# UVS-SCH-1.net
KiCad netlist of a schematic drawn in Altium Designer
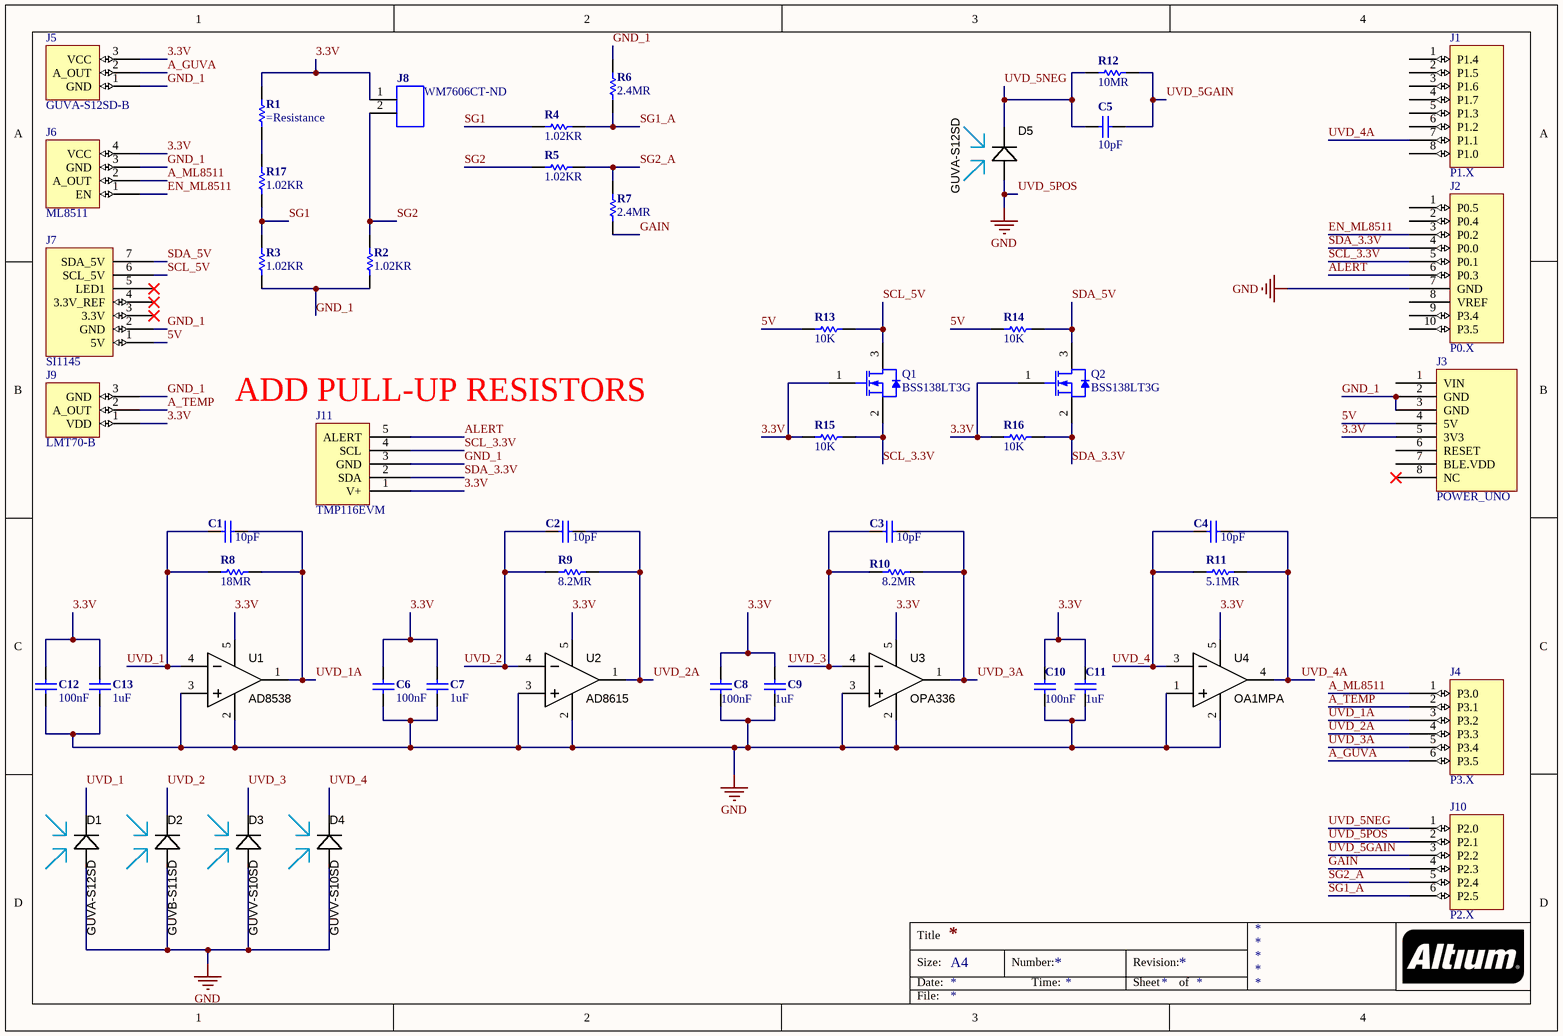
[diagram p0: UVS-SCH-1.SchDoc]

(export (version "E")
  (design (tool "Eeschema 10.0.6"))
  (components
    (comp (ref "C1")
      (value "10pF")
      (footprint "CAP-0805(2012)-R")
      (description "___ OHM ___ mW 0805(2012) SMD")
      (fields
        (field (name "MANUFACTURER") "Kemet")
        (field (name "MANUFACTURER PART NUMBER") "C0805C100J5GAC-TU")
      )
      (libsource (lib "UVS-Schlib") (part "C-0805(2012)"))
    )
    (comp (ref "C2")
      (value "10pF")
      (footprint "CAP-0805(2012)-R")
      (description "___ OHM ___ mW 0805(2012) SMD")
      (fields
        (field (name "MANUFACTURER") "Kemet")
        (field (name "MANUFACTURER PART NUMBER") "C0805C100J5GAC-TU")
      )
      (libsource (lib "UVS-Schlib") (part "C-0805(2012)"))
    )
    (comp (ref "C3")
      (value "10pF")
      (footprint "CAP-0805(2012)-R")
      (description "___ OHM ___ mW 0805(2012) SMD")
      (fields
        (field (name "MANUFACTURER") "Kemet")
        (field (name "MANUFACTURER PART NUMBER") "C0805C100J5GAC-TU")
      )
      (libsource (lib "UVS-Schlib") (part "C-0805(2012)"))
    )
    (comp (ref "C4")
      (value "10pF")
      (footprint "CAP-0805(2012)-R")
      (description "___ OHM ___ mW 0805(2012) SMD")
      (fields
        (field (name "MANUFACTURER") "Kemet")
        (field (name "MANUFACTURER PART NUMBER") "C0805C100J5GAC-TU")
      )
      (libsource (lib "UVS-Schlib") (part "C-0805(2012)"))
    )
    (comp (ref "C5")
      (value "10pF")
      (footprint "CAP-0805(2012)-R")
      (description "___ OHM ___ mW 0805(2012) SMD")
      (fields
        (field (name "MANUFACTURER") "KEMET")
        (field (name "MANUFACTURER PART NUMBER") "C0805C100J5GAC-TU")
      )
      (libsource (lib "UVS-Schlib") (part "C-0805(2012)"))
    )
    (comp (ref "C6")
      (value "100nF")
      (footprint "CAP-0805(2012)-R")
      (description "___ OHM ___ mW 0805(2012) SMD")
      (fields
        (field (name "MANUFACTURER") "Yageo")
        (field (name "MANUFACTURER PART NUMBER") "CC0805KRX7R9BB104")
      )
      (libsource (lib "UVS-Schlib") (part "C-0805(2012)"))
    )
    (comp (ref "C7")
      (value "1uF")
      (footprint "CAP-0805(2012)-R")
      (description "___ OHM ___ mW 0805(2012) SMD")
      (fields
        (field (name "MANUFACTURER") "Yageo")
        (field (name "MANUFACTURER PART NUMBER") "CC0805KKX7R7BB105")
      )
      (libsource (lib "UVS-Schlib") (part "C-0805(2012)"))
    )
    (comp (ref "C8")
      (value "100nF")
      (footprint "CAP-0805(2012)-R")
      (description "___ OHM ___ mW 0805(2012) SMD")
      (fields
        (field (name "MANUFACTURER") "Yageo")
        (field (name "MANUFACTURER PART NUMBER") "CC0805KRX7R9BB104")
      )
      (libsource (lib "UVS-Schlib") (part "C-0805(2012)"))
    )
    (comp (ref "C9")
      (value "1uF")
      (footprint "CAP-0805(2012)-R")
      (description "___ OHM ___ mW 0805(2012) SMD")
      (fields
        (field (name "MANUFACTURER") "Yageo")
        (field (name "MANUFACTURER PART NUMBER") "CC0805KKX7R7BB105")
      )
      (libsource (lib "UVS-Schlib") (part "C-0805(2012)"))
    )
    (comp (ref "C10")
      (value "100nF")
      (footprint "CAP-0805(2012)-R")
      (description "___ OHM ___ mW 0805(2012) SMD")
      (fields
        (field (name "MANUFACTURER") "Yageo")
        (field (name "MANUFACTURER PART NUMBER") "CC0805KRX7R9BB104")
      )
      (libsource (lib "UVS-Schlib") (part "C-0805(2012)"))
    )
    (comp (ref "C11")
      (value "1uF")
      (footprint "CAP-0805(2012)-R")
      (description "___ OHM ___ mW 0805(2012) SMD")
      (fields
        (field (name "MANUFACTURER") "Yageo")
        (field (name "MANUFACTURER PART NUMBER") "CC0805KKX7R7BB105")
      )
      (libsource (lib "UVS-Schlib") (part "C-0805(2012)"))
    )
    (comp (ref "C12")
      (value "100nF")
      (footprint "CAP-0805(2012)-R")
      (description "___ OHM ___ mW 0805(2012) SMD")
      (fields
        (field (name "MANUFACTURER") "Yageo")
        (field (name "MANUFACTURER PART NUMBER") "CC0805KRX7R9BB104")
      )
      (libsource (lib "UVS-Schlib") (part "C-0805(2012)"))
    )
    (comp (ref "C13")
      (value "1uF")
      (footprint "CAP-0805(2012)-R")
      (description "___ OHM ___ mW 0805(2012) SMD")
      (fields
        (field (name "MANUFACTURER") "Yageo")
        (field (name "MANUFACTURER PART NUMBER") "CC0805KKX7R7BB105")
      )
      (libsource (lib "UVS-Schlib") (part "C-0805(2012)"))
    )
    (comp (ref "D1")
      (value "GUVA-S12SD")
      (footprint "SMD 3528")
      (description "UV Photodiode, 3528 SMD")
      (libsource (lib "UVS-Schlib") (part "GUVA-S12SD"))
    )
    (comp (ref "D2")
      (value "GUVB-S11SD")
      (footprint "SMD 3528")
      (description "UV Photodiode, 3528 SMD")
      (libsource (lib "UVS-Schlib") (part "GUVB-S11SD"))
    )
    (comp (ref "D3")
      (value "GUVV-S10SD")
      (footprint "SMD 3528")
      (description "UV Photodiode, 3528 SMD")
      (libsource (lib "UVS-Schlib") (part "GUVV-S10SD"))
    )
    (comp (ref "D4")
      (value "GUVV-S10SD")
      (footprint "SMD 3528")
      (description "UV Photodiode, 3528 SMD")
      (libsource (lib "UVS-Schlib") (part "GUVV-S10SD"))
    )
    (comp (ref "D5")
      (value "GUVA-S12SD")
      (footprint "SMD 3528")
      (description "UV Photodiode, 3528 SMD")
      (libsource (lib "UVS-Schlib") (part "GUVA-S12SD"))
    )
    (comp (ref "J1")
      (value "P1.X")
      (footprint "Header 8x1 8.5mm")
      (libsource (lib "UVS-Schlib") (part "IOL"))
    )
    (comp (ref "J2")
      (value "P0.X")
      (footprint "Header 10x1 8.5mm")
      (libsource (lib "UVS-Schlib") (part "IOH"))
    )
    (comp (ref "J3")
      (value "POWER_UNO")
      (footprint "Header 8x1 8.5mm")
      (libsource (lib "UVS-Schlib") (part "POWER_UNO"))
    )
    (comp (ref "J4") (value "P3.X") (footprint "Header 6x1 8.5mm") (libsource (lib "UVS-Schlib") (part "AD")))
    (comp (ref "J5")
      (value "GUVA-S12SD-B")
      (footprint "UVS-PcbLib:Header 3x1 8.5mm")
      (description "UV Light Sensor Breakout Board")
      (libsource (lib "UVS-Schlib") (part "GUVA-S12SD-B"))
    )
    (comp (ref "J6")
      (value "ML8511")
      (footprint "UVS-PcbLib:Header 4x1 8.5mm")
      (description "UV Light Sensor Breakout Board")
      (libsource (lib "UVS-Schlib") (part "ML8511"))
    )
    (comp (ref "J7")
      (value "SI1145")
      (footprint "UVS-PcbLib:Header 7x1 8.5mm")
      (description "UV Light Sensor Digital")
      (libsource (lib "UVS-Schlib") (part "SI1145"))
    )
    (comp (ref "J8")
      (value "Header 2 pin")
      (footprint "WM7606CT-ND")
      (description "Header, 2 pin, .1 pitch")
      (fields
        (field (name "MANUFACTURER") "Molex, LLC")
        (field (name "MANUFACTURER PART NUMBER") "0533980271")
        (field (name "SUPPLIER PART NUMBER 1") "WM7606CT-ND")
      )
      (libsource (lib "UVS-Schlib") (part "CON-2Pin"))
    )
    (comp (ref "J9")
      (value "LMT70-B")
      (footprint "UVS-PcbLib:Header 3x1 8.5mm")
      (description "Precision Analog Temperature Sensor")
      (libsource (lib "UVS-Schlib") (part "LMT70-B"))
    )
    (comp (ref "J10")
      (value "P2.X")
      (footprint "Header 6x1 8.5mm")
      (libsource (lib "UVS-Schlib") (part "P2.X"))
    )
    (comp (ref "J11")
      (value "TMP116EVM")
      (footprint "Header 5x1 8.5mm")
      (libsource (lib "UVS-Schlib") (part "TMP116EVM"))
    )
    (comp (ref "Q1")
      (value "BSS138LT3G")
      (footprint "ONSC-SOT-23-3-318-08_V")
      (description "Power MOSFET, 200 mA, 50 V, N-Channel, 3-Pin SOT-23, Pb-Free, Tape and Reel")
      (fields (field (name "MANUFACTURER") "ON Semiconductor"))
      (libsource (lib "Altium Content Vault") (part "CMP-1058-00765-1"))
    )
    (comp (ref "Q2")
      (value "BSS138LT3G")
      (footprint "ONSC-SOT-23-3-318-08_V")
      (description "Power MOSFET, 200 mA, 50 V, N-Channel, 3-Pin SOT-23, Pb-Free, Tape and Reel")
      (fields (field (name "MANUFACTURER") "ON Semiconductor"))
      (libsource (lib "Altium Content Vault") (part "CMP-1058-00765-1"))
    )
    (comp (ref "R1")
      (value "~")
      (footprint "R-0805(2012)-R")
      (description "___ OHM ___ mW 0805(2012) SMD")
      (libsource (lib "UVS-Schlib") (part "R-0805(2012)"))
    )
    (comp (ref "R2")
      (value "1.02KR")
      (footprint "R-0805(2012)-R")
      (description "___ OHM ___ mW 0805(2012) SMD")
      (fields
        (field (name "MANUFACTURER") "Panasonic")
        (field (name "MANUFACTURER PART NUMBER") "ERA6AEB1021V")
      )
      (libsource (lib "UVS-Schlib") (part "R-0805(2012)"))
    )
    (comp (ref "R3")
      (value "1.02KR")
      (footprint "R-0805(2012)-R")
      (description "___ OHM ___ mW 0805(2012) SMD")
      (fields
        (field (name "MANUFACTURER") "Panasonic")
        (field (name "MANUFACTURER PART NUMBER") "ERA6AEB1021V")
      )
      (libsource (lib "UVS-Schlib") (part "R-0805(2012)"))
    )
    (comp (ref "R4")
      (value "1.02KR")
      (footprint "R-0805(2012)-R")
      (description "___ OHM ___ mW 0805(2012) SMD")
      (fields
        (field (name "MANUFACTURER") "Panasonic")
        (field (name "MANUFACTURER PART NUMBER") "ERA6AEB1021V")
      )
      (libsource (lib "UVS-Schlib") (part "R-0805(2012)"))
    )
    (comp (ref "R5")
      (value "1.02KR")
      (footprint "R-0805(2012)-R")
      (description "___ OHM ___ mW 0805(2012) SMD")
      (fields
        (field (name "MANUFACTURER") "Panasonic")
        (field (name "MANUFACTURER PART NUMBER") "ERA6AEB1021V")
      )
      (libsource (lib "UVS-Schlib") (part "R-0805(2012)"))
    )
    (comp (ref "R6")
      (value "2.4MR")
      (footprint "R-0805(2012)-R")
      (description "___ OHM ___ mW 0805(2012) SMD")
      (fields
        (field (name "MANUFACTURER") "Panasonic ECG")
        (field (name "MANUFACTURER PART NUMBER") "ERJ-6GEYJ245V")
      )
      (libsource (lib "UVS-Schlib") (part "R-0805(2012)"))
    )
    (comp (ref "R7")
      (value "2.4MR")
      (footprint "R-0805(2012)-R")
      (description "___ OHM ___ mW 0805(2012) SMD")
      (fields
        (field (name "MANUFACTURER") "Panasonic ECG")
        (field (name "MANUFACTURER PART NUMBER") "ERJ-6GEYJ245V")
      )
      (libsource (lib "UVS-Schlib") (part "R-0805(2012)"))
    )
    (comp (ref "R8")
      (value "18MR")
      (footprint "R-0805(2012)-R")
      (description "___ OHM ___ mW 0805(2012) SMD")
      (fields
        (field (name "MANUFACTURER") "Yageo")
        (field (name "MANUFACTURER PART NUMBER") "RC0805JR-0718ML")
      )
      (libsource (lib "UVS-Schlib") (part "R-0805(2012)"))
    )
    (comp (ref "R9")
      (value "8.2MR")
      (footprint "R-0805(2012)-R")
      (description "___ OHM ___ mW 0805(2012) SMD")
      (fields
        (field (name "MANUFACTURER") "Yageo")
        (field (name "MANUFACTURER PART NUMBER") "RC0805FR-078M2L")
      )
      (libsource (lib "UVS-Schlib") (part "R-0805(2012)"))
    )
    (comp (ref "R10")
      (value "8.2MR")
      (footprint "R-0805(2012)-R")
      (description "___ OHM ___ mW 0805(2012) SMD")
      (fields
        (field (name "MANUFACTURER") "Yageo")
        (field (name "MANUFACTURER PART NUMBER") "RC0805FR-078M2L")
      )
      (libsource (lib "UVS-Schlib") (part "R-0805(2012)"))
    )
    (comp (ref "R11")
      (value "5.1MR")
      (footprint "R-0805(2012)-R")
      (description "___ OHM ___ mW 0805(2012) SMD")
      (fields
        (field (name "MANUFACTURER") "Yageo")
        (field (name "MANUFACTURER PART NUMBER") "RC0805FR-075M1L")
      )
      (libsource (lib "UVS-Schlib") (part "R-0805(2012)"))
    )
    (comp (ref "R12")
      (value "10MR")
      (footprint "R-0805(2012)-R")
      (description "___ OHM ___ mW 0805(2012) SMD")
      (fields
        (field (name "MANUFACTURER") "Yageo")
        (field (name "MANUFACTURER PART NUMBER") "RC0805JR-0710ML")
      )
      (libsource (lib "UVS-Schlib") (part "R-0805(2012)"))
    )
    (comp (ref "R13")
      (value "10K")
      (footprint "R-0805(2012)-R")
      (description "___ OHM ___ mW 0805(2012) SMD")
      (fields
        (field (name "MANUFACTURER") "Yageo")
        (field (name "MANUFACTURER PART NUMBER") "RC0805FR-0710KL")
      )
      (libsource (lib "UVS-Schlib") (part "R-0805(2012)"))
    )
    (comp (ref "R14")
      (value "10K")
      (footprint "R-0805(2012)-R")
      (description "___ OHM ___ mW 0805(2012) SMD")
      (fields
        (field (name "MANUFACTURER") "Yageo")
        (field (name "MANUFACTURER PART NUMBER") "RC0805FR-0710KL")
      )
      (libsource (lib "UVS-Schlib") (part "R-0805(2012)"))
    )
    (comp (ref "R15")
      (value "10K")
      (footprint "R-0805(2012)-R")
      (description "___ OHM ___ mW 0805(2012) SMD")
      (fields
        (field (name "MANUFACTURER") "Yageo")
        (field (name "MANUFACTURER PART NUMBER") "RC0805FR-0710KL")
      )
      (libsource (lib "UVS-Schlib") (part "R-0805(2012)"))
    )
    (comp (ref "R16")
      (value "10K")
      (footprint "R-0805(2012)-R")
      (description "___ OHM ___ mW 0805(2012) SMD")
      (fields
        (field (name "MANUFACTURER") "Yageo")
        (field (name "MANUFACTURER PART NUMBER") "RC0805FR-0710KL")
      )
      (libsource (lib "UVS-Schlib") (part "R-0805(2012)"))
    )
    (comp (ref "R17")
      (value "1.02KR")
      (footprint "R-0805(2012)-R")
      (description "___ OHM ___ mW 0805(2012) SMD")
      (fields
        (field (name "MANUFACTURER") "Panasonic")
        (field (name "MANUFACTURER PART NUMBER") "ERA6AEB1021V")
      )
      (libsource (lib "UVS-Schlib") (part "R-0805(2012)"))
    )
    (comp (ref "U1")
      (value "AD8538")
      (footprint "SOT23-5")
      (description "IC SMD Atuo-Zero Op Amp Precision, Low Power")
      (fields
        (field (name "MANUFACTURER") "Analog Devices")
        (field (name "MANUFACTURER PART NUMBER") "AD8538AUJZ-REEL7")
      )
      (libsource (lib "UVS-Schlib") (part "AD8538"))
    )
    (comp (ref "U2")
      (value "AD8615")
      (footprint "SOT23-5")
      (description "IC SMD Transimpedance Op Amp Precision")
      (fields
        (field (name "MANUFACTURER") "Analog Devices")
        (field (name "MANUFACTURER PART NUMBER") "AD8615AUJZ-REEL7")
      )
      (libsource (lib "UVS-Schlib") (part "AD8615"))
    )
    (comp (ref "U3")
      (value "OPA336")
      (footprint "SOT23-5")
      (fields
        (field (name "MANUFACTURER") "Texas Instruments")
        (field (name "MANUFACTURER PART NUMBER") "OPA336NA/3K")
      )
      (libsource (lib "UVS-Schlib") (part "OPA336"))
    )
    (comp (ref "U4")
      (value "OA1MPA")
      (footprint "SC70-5L")
      (fields
        (field (name "MANUFACTURER") "STMicroelectronics")
        (field (name "MANUFACTURER PART NUMBER") "OA1MPA22C")
      )
      (libsource (lib "UVS-Schlib") (part "OA1MPA"))
    )
  )
  (nets
    (net (code "1") (name "/3.3V") (class "Default")
      (node (ref "C10") (pin "1") (pinfunction "1_1") (pintype "passive"))
      (node (ref "C11") (pin "1") (pinfunction "1_1") (pintype "passive"))
      (node (ref "C12") (pin "1") (pinfunction "1_1") (pintype "passive"))
      (node (ref "C13") (pin "1") (pinfunction "1_1") (pintype "passive"))
      (node (ref "C6") (pin "1") (pinfunction "1_1") (pintype "passive"))
      (node (ref "C7") (pin "1") (pinfunction "1_1") (pintype "passive"))
      (node (ref "C8") (pin "1") (pinfunction "1_1") (pintype "passive"))
      (node (ref "C9") (pin "1") (pinfunction "1_1") (pintype "passive"))
      (node (ref "J11") (pin "1") (pinfunction "V+_1") (pintype "passive"))
      (node (ref "J3") (pin "5") (pinfunction "3V3_5") (pintype "power_in"))
      (node (ref "J5") (pin "3") (pinfunction "VCC_3") (pintype "bidirectional"))
      (node (ref "J6") (pin "4") (pinfunction "VCC_4") (pintype "bidirectional"))
      (node (ref "J8") (pin "1") (pinfunction "1_1") (pintype "passive"))
      (node (ref "J9") (pin "1") (pinfunction "VDD_1") (pintype "bidirectional"))
      (node (ref "Q1") (pin "1") (pinfunction "G_1") (pintype "passive"))
      (node (ref "Q2") (pin "1") (pinfunction "G_1") (pintype "passive"))
      (node (ref "R1") (pin "1") (pinfunction "1_1") (pintype "passive"))
      (node (ref "R15") (pin "1") (pinfunction "1_1") (pintype "passive"))
      (node (ref "R16") (pin "1") (pinfunction "1_1") (pintype "passive"))
      (node (ref "U1") (pin "5") (pinfunction "V+_5") (pintype "passive"))
      (node (ref "U2") (pin "5") (pinfunction "V+_5") (pintype "passive"))
      (node (ref "U3") (pin "5") (pinfunction "V+_5") (pintype "passive"))
      (node (ref "U4") (pin "5") (pinfunction "V+_5") (pintype "passive"))
    )
    (net (code "2") (name "/5V") (class "Default")
      (node (ref "J3") (pin "4") (pinfunction "5V_4") (pintype "power_in"))
      (node (ref "J7") (pin "1") (pinfunction "5V_1") (pintype "bidirectional"))
      (node (ref "R13") (pin "1") (pinfunction "1_1") (pintype "passive"))
      (node (ref "R14") (pin "1") (pinfunction "1_1") (pintype "passive"))
    )
    (net (code "3") (name "/ALERT") (class "Default")
      (node (ref "J11") (pin "5") (pinfunction "ALERT_5") (pintype "passive"))
      (node (ref "J2") (pin "6") (pinfunction "P0.3_6") (pintype "bidirectional"))
    )
    (net (code "4") (name "/A_GUVA") (class "Default")
      (node (ref "J4") (pin "6") (pinfunction "P3.5_6") (pintype "bidirectional"))
      (node (ref "J5") (pin "2") (pinfunction "A_OUT_2") (pintype "bidirectional"))
    )
    (net (code "5") (name "/A_ML8511") (class "Default")
      (node (ref "J4") (pin "1") (pinfunction "P3.0_1") (pintype "bidirectional"))
      (node (ref "J6") (pin "2") (pinfunction "A_OUT_2") (pintype "bidirectional"))
    )
    (net (code "6") (name "/A_TEMP") (class "Default")
      (node (ref "J4") (pin "2") (pinfunction "P3.1_2") (pintype "bidirectional"))
      (node (ref "J9") (pin "2") (pinfunction "A_OUT_2") (pintype "bidirectional"))
    )
    (net (code "7") (name "/EN_ML8511") (class "Default")
      (node (ref "J2") (pin "3") (pinfunction "P0.2_3") (pintype "bidirectional"))
      (node (ref "J6") (pin "1") (pinfunction "EN_1") (pintype "bidirectional"))
    )
    (net (code "8") (name "/GAIN") (class "Default")
      (node (ref "J10") (pin "4") (pinfunction "P2.3_4") (pintype "bidirectional"))
      (node (ref "R7") (pin "2") (pinfunction "2_2") (pintype "passive"))
    )
    (net (code "9") (name "/GND_1") (class "Default")
      (node (ref "J11") (pin "3") (pinfunction "GND_3") (pintype "passive"))
      (node (ref "J3") (pin "2") (pinfunction "GND_2") (pintype "power_in"))
      (node (ref "J3") (pin "3") (pinfunction "GND_3") (pintype "power_in"))
      (node (ref "J5") (pin "1") (pinfunction "GND_1") (pintype "bidirectional"))
      (node (ref "J6") (pin "3") (pinfunction "GND_3") (pintype "bidirectional"))
      (node (ref "J7") (pin "2") (pinfunction "GND_2") (pintype "bidirectional"))
      (node (ref "J9") (pin "3") (pinfunction "GND_3") (pintype "bidirectional"))
      (node (ref "R2") (pin "2") (pinfunction "2_2") (pintype "passive"))
      (node (ref "R3") (pin "2") (pinfunction "2_2") (pintype "passive"))
      (node (ref "R6") (pin "1") (pinfunction "1_1") (pintype "passive"))
    )
    (net (code "10") (name "/SCL_3.3V") (class "Default")
      (node (ref "J11") (pin "4") (pinfunction "SCL_4") (pintype "passive"))
      (node (ref "J2") (pin "5") (pinfunction "P0.1_5") (pintype "bidirectional"))
      (node (ref "Q1") (pin "2") (pinfunction "S_2") (pintype "passive"))
      (node (ref "R15") (pin "2") (pinfunction "2_2") (pintype "passive"))
    )
    (net (code "11") (name "/SCL_5V") (class "Default")
      (node (ref "J7") (pin "6") (pinfunction "SCL_5V_6") (pintype "passive"))
      (node (ref "Q1") (pin "3") (pinfunction "D_3") (pintype "passive"))
      (node (ref "R13") (pin "2") (pinfunction "2_2") (pintype "passive"))
    )
    (net (code "12") (name "/SDA_3.3V") (class "Default")
      (node (ref "J11") (pin "2") (pinfunction "SDA_2") (pintype "passive"))
      (node (ref "J2") (pin "4") (pinfunction "P0.0_4") (pintype "bidirectional"))
      (node (ref "Q2") (pin "2") (pinfunction "S_2") (pintype "passive"))
      (node (ref "R16") (pin "2") (pinfunction "2_2") (pintype "passive"))
    )
    (net (code "13") (name "/SDA_5V") (class "Default")
      (node (ref "J7") (pin "7") (pinfunction "SDA_5V_7") (pintype "passive"))
      (node (ref "Q2") (pin "3") (pinfunction "D_3") (pintype "passive"))
      (node (ref "R14") (pin "2") (pinfunction "2_2") (pintype "passive"))
    )
    (net (code "14") (name "/SG1") (class "Default")
      (node (ref "R17") (pin "2") (pinfunction "2_2") (pintype "passive"))
      (node (ref "R3") (pin "1") (pinfunction "1_1") (pintype "passive"))
      (node (ref "R4") (pin "1") (pinfunction "1_1") (pintype "passive"))
    )
    (net (code "15") (name "/SG1_A") (class "Default")
      (node (ref "J10") (pin "6") (pinfunction "P2.5_6") (pintype "bidirectional"))
      (node (ref "R4") (pin "2") (pinfunction "2_2") (pintype "passive"))
      (node (ref "R6") (pin "2") (pinfunction "2_2") (pintype "passive"))
    )
    (net (code "16") (name "/SG2") (class "Default")
      (node (ref "J8") (pin "2") (pinfunction "2_2") (pintype "passive"))
      (node (ref "R2") (pin "1") (pinfunction "1_1") (pintype "passive"))
      (node (ref "R5") (pin "1") (pinfunction "1_1") (pintype "passive"))
    )
    (net (code "17") (name "/SG2_A") (class "Default")
      (node (ref "J10") (pin "5") (pinfunction "P2.4_5") (pintype "bidirectional"))
      (node (ref "R5") (pin "2") (pinfunction "2_2") (pintype "passive"))
      (node (ref "R7") (pin "1") (pinfunction "1_1") (pintype "passive"))
    )
    (net (code "18") (name "/UVD_1") (class "Default")
      (node (ref "C1") (pin "1") (pinfunction "1_1") (pintype "passive"))
      (node (ref "D1") (pin "K") (pinfunction "K_K") (pintype "passive"))
      (node (ref "R8") (pin "1") (pinfunction "1_1") (pintype "passive"))
      (node (ref "U1") (pin "4") (pinfunction "IN-_4") (pintype "passive"))
    )
    (net (code "19") (name "/UVD_1A") (class "Default")
      (node (ref "C1") (pin "2") (pinfunction "2_2") (pintype "passive"))
      (node (ref "J4") (pin "3") (pinfunction "P3.2_3") (pintype "bidirectional"))
      (node (ref "R8") (pin "2") (pinfunction "2_2") (pintype "passive"))
      (node (ref "U1") (pin "1") (pinfunction "OUT_1") (pintype "passive"))
    )
    (net (code "20") (name "/UVD_2") (class "Default")
      (node (ref "C2") (pin "1") (pinfunction "1_1") (pintype "passive"))
      (node (ref "D2") (pin "K") (pinfunction "K_K") (pintype "passive"))
      (node (ref "R9") (pin "1") (pinfunction "1_1") (pintype "passive"))
      (node (ref "U2") (pin "4") (pinfunction "IN-_4") (pintype "passive"))
    )
    (net (code "21") (name "/UVD_2A") (class "Default")
      (node (ref "C2") (pin "2") (pinfunction "2_2") (pintype "passive"))
      (node (ref "J4") (pin "4") (pinfunction "P3.3_4") (pintype "bidirectional"))
      (node (ref "R9") (pin "2") (pinfunction "2_2") (pintype "passive"))
      (node (ref "U2") (pin "1") (pinfunction "OUT_1") (pintype "passive"))
    )
    (net (code "22") (name "/UVD_3") (class "Default")
      (node (ref "C3") (pin "1") (pinfunction "1_1") (pintype "passive"))
      (node (ref "D3") (pin "K") (pinfunction "K_K") (pintype "passive"))
      (node (ref "R10") (pin "1") (pinfunction "1_1") (pintype "passive"))
      (node (ref "U3") (pin "4") (pinfunction "IN-_4") (pintype "passive"))
    )
    (net (code "23") (name "/UVD_3A") (class "Default")
      (node (ref "C3") (pin "2") (pinfunction "2_2") (pintype "passive"))
      (node (ref "J4") (pin "5") (pinfunction "P3.4_5") (pintype "bidirectional"))
      (node (ref "R10") (pin "2") (pinfunction "2_2") (pintype "passive"))
      (node (ref "U3") (pin "1") (pinfunction "OUT_1") (pintype "passive"))
    )
    (net (code "24") (name "/UVD_4") (class "Default")
      (node (ref "C4") (pin "1") (pinfunction "1_1") (pintype "passive"))
      (node (ref "D4") (pin "K") (pinfunction "K_K") (pintype "passive"))
      (node (ref "R11") (pin "1") (pinfunction "1_1") (pintype "passive"))
      (node (ref "U4") (pin "3") (pinfunction "IN+_3") (pintype "passive"))
    )
    (net (code "25") (name "/UVD_4A") (class "Default")
      (node (ref "C4") (pin "2") (pinfunction "2_2") (pintype "passive"))
      (node (ref "J1") (pin "7") (pinfunction "P1.1_7") (pintype "bidirectional"))
      (node (ref "R11") (pin "2") (pinfunction "2_2") (pintype "passive"))
      (node (ref "U4") (pin "4") (pinfunction "IN-_4") (pintype "passive"))
    )
    (net (code "26") (name "/UVD_5GAIN") (class "Default")
      (node (ref "C5") (pin "2") (pinfunction "2_2") (pintype "passive"))
      (node (ref "J10") (pin "3") (pinfunction "P2.2_3") (pintype "bidirectional"))
      (node (ref "R12") (pin "2") (pinfunction "2_2") (pintype "passive"))
    )
    (net (code "27") (name "/UVD_5NEG") (class "Default")
      (node (ref "C5") (pin "1") (pinfunction "1_1") (pintype "passive"))
      (node (ref "D5") (pin "K") (pinfunction "K_K") (pintype "passive"))
      (node (ref "J10") (pin "1") (pinfunction "P2.0_1") (pintype "bidirectional"))
      (node (ref "R12") (pin "1") (pinfunction "1_1") (pintype "passive"))
    )
    (net (code "28") (name "GND") (class "Default")
      (node (ref "C10") (pin "2") (pinfunction "2_2") (pintype "passive"))
      (node (ref "C11") (pin "2") (pinfunction "2_2") (pintype "passive"))
      (node (ref "C12") (pin "2") (pinfunction "2_2") (pintype "passive"))
      (node (ref "C13") (pin "2") (pinfunction "2_2") (pintype "passive"))
      (node (ref "C6") (pin "2") (pinfunction "2_2") (pintype "passive"))
      (node (ref "C7") (pin "2") (pinfunction "2_2") (pintype "passive"))
      (node (ref "C8") (pin "2") (pinfunction "2_2") (pintype "passive"))
      (node (ref "C9") (pin "2") (pinfunction "2_2") (pintype "passive"))
      (node (ref "D1") (pin "A") (pinfunction "A_A") (pintype "passive"))
      (node (ref "D2") (pin "A") (pinfunction "A_A") (pintype "passive"))
      (node (ref "D3") (pin "A") (pinfunction "A_A") (pintype "passive"))
      (node (ref "D4") (pin "A") (pinfunction "A_A") (pintype "passive"))
      (node (ref "D5") (pin "A") (pinfunction "A_A") (pintype "passive"))
      (node (ref "J10") (pin "2") (pinfunction "P2.1_2") (pintype "bidirectional"))
      (node (ref "J2") (pin "7") (pinfunction "GND_7") (pintype "power_in"))
      (node (ref "U1") (pin "2") (pinfunction "V-_2") (pintype "passive"))
      (node (ref "U1") (pin "3") (pinfunction "IN+_3") (pintype "passive"))
      (node (ref "U2") (pin "2") (pinfunction "V-_2") (pintype "passive"))
      (node (ref "U2") (pin "3") (pinfunction "IN+_3") (pintype "passive"))
      (node (ref "U3") (pin "2") (pinfunction "V-_2") (pintype "passive"))
      (node (ref "U3") (pin "3") (pinfunction "IN+_3") (pintype "passive"))
      (node (ref "U4") (pin "1") (pinfunction "OUT_1") (pintype "passive"))
      (node (ref "U4") (pin "2") (pinfunction "V-_2") (pintype "passive"))
    )
    (net (code "29") (name "Net-(R1-Pad2)") (class "Default")
      (node (ref "R1") (pin "2") (pinfunction "2_2") (pintype "passive"))
      (node (ref "R17") (pin "1") (pinfunction "1_1") (pintype "passive"))
    )
    (net (code "30") (name "unconnected-(J1-P1.0-Pad8)") (class "Default")
      (node (ref "J1") (pin "8") (pinfunction "P1.0_8") (pintype "bidirectional"))
    )
    (net (code "31") (name "unconnected-(J1-P1.2-Pad6)") (class "Default")
      (node (ref "J1") (pin "6") (pinfunction "P1.2_6") (pintype "bidirectional"))
    )
    (net (code "32") (name "unconnected-(J1-P1.3-Pad5)") (class "Default")
      (node (ref "J1") (pin "5") (pinfunction "P1.3_5") (pintype "bidirectional"))
    )
    (net (code "33") (name "unconnected-(J1-P1.4-Pad1)") (class "Default")
      (node (ref "J1") (pin "1") (pinfunction "P1.4_1") (pintype "bidirectional"))
    )
    (net (code "34") (name "unconnected-(J1-P1.5-Pad2)") (class "Default")
      (node (ref "J1") (pin "2") (pinfunction "P1.5_2") (pintype "bidirectional"))
    )
    (net (code "35") (name "unconnected-(J1-P1.6-Pad3)") (class "Default")
      (node (ref "J1") (pin "3") (pinfunction "P1.6_3") (pintype "bidirectional"))
    )
    (net (code "36") (name "unconnected-(J1-P1.7-Pad4)") (class "Default")
      (node (ref "J1") (pin "4") (pinfunction "P1.7_4") (pintype "bidirectional"))
    )
    (net (code "37") (name "unconnected-(J2-P0.4-Pad2)") (class "Default")
      (node (ref "J2") (pin "2") (pinfunction "P0.4_2") (pintype "bidirectional"))
    )
    (net (code "38") (name "unconnected-(J2-P0.5-Pad1)") (class "Default")
      (node (ref "J2") (pin "1") (pinfunction "P0.5_1") (pintype "bidirectional"))
    )
    (net (code "39") (name "unconnected-(J2-P3.4-Pad9)") (class "Default")
      (node (ref "J2") (pin "9") (pinfunction "P3.4_9") (pintype "bidirectional"))
    )
    (net (code "40") (name "unconnected-(J2-P3.5-Pad10)") (class "Default")
      (node (ref "J2") (pin "10") (pinfunction "P3.5_10") (pintype "bidirectional"))
    )
    (net (code "41") (name "unconnected-(J2-VREF-Pad8)") (class "Default")
      (node (ref "J2") (pin "8") (pinfunction "VREF_8") (pintype "passive"))
    )
    (net (code "42") (name "unconnected-(J3-BLE.VDD-Pad7)") (class "Default")
      (node (ref "J3") (pin "7") (pinfunction "BLE.VDD_7") (pintype "power_in"))
    )
    (net (code "43") (name "unconnected-(J3-NC-Pad8)") (class "Default")
      (node (ref "J3") (pin "8") (pinfunction "NC_8") (pintype "passive+no_connect"))
    )
    (net (code "44") (name "unconnected-(J3-RESET-Pad6)") (class "Default")
      (node (ref "J3") (pin "6") (pinfunction "RESET_6") (pintype "passive"))
    )
    (net (code "45") (name "unconnected-(J3-VIN-Pad1)") (class "Default")
      (node (ref "J3") (pin "1") (pinfunction "VIN_1") (pintype "power_in"))
    )
    (net (code "46") (name "unconnected-(J7-3.3V-Pad3)") (class "Default")
      (node (ref "J7") (pin "3") (pinfunction "3.3V_3") (pintype "bidirectional+no_connect"))
    )
    (net (code "47") (name "unconnected-(J7-3.3V_REF-Pad4)") (class "Default")
      (node (ref "J7") (pin "4") (pinfunction "3.3V_REF_4") (pintype "bidirectional+no_connect"))
    )
    (net (code "48") (name "unconnected-(J7-LED1-Pad5)") (class "Default")
      (node (ref "J7") (pin "5") (pinfunction "LED1_5") (pintype "passive+no_connect"))
    )
  )
)
